# USB.net
KiCad netlist of a schematic drawn in Altium Designer
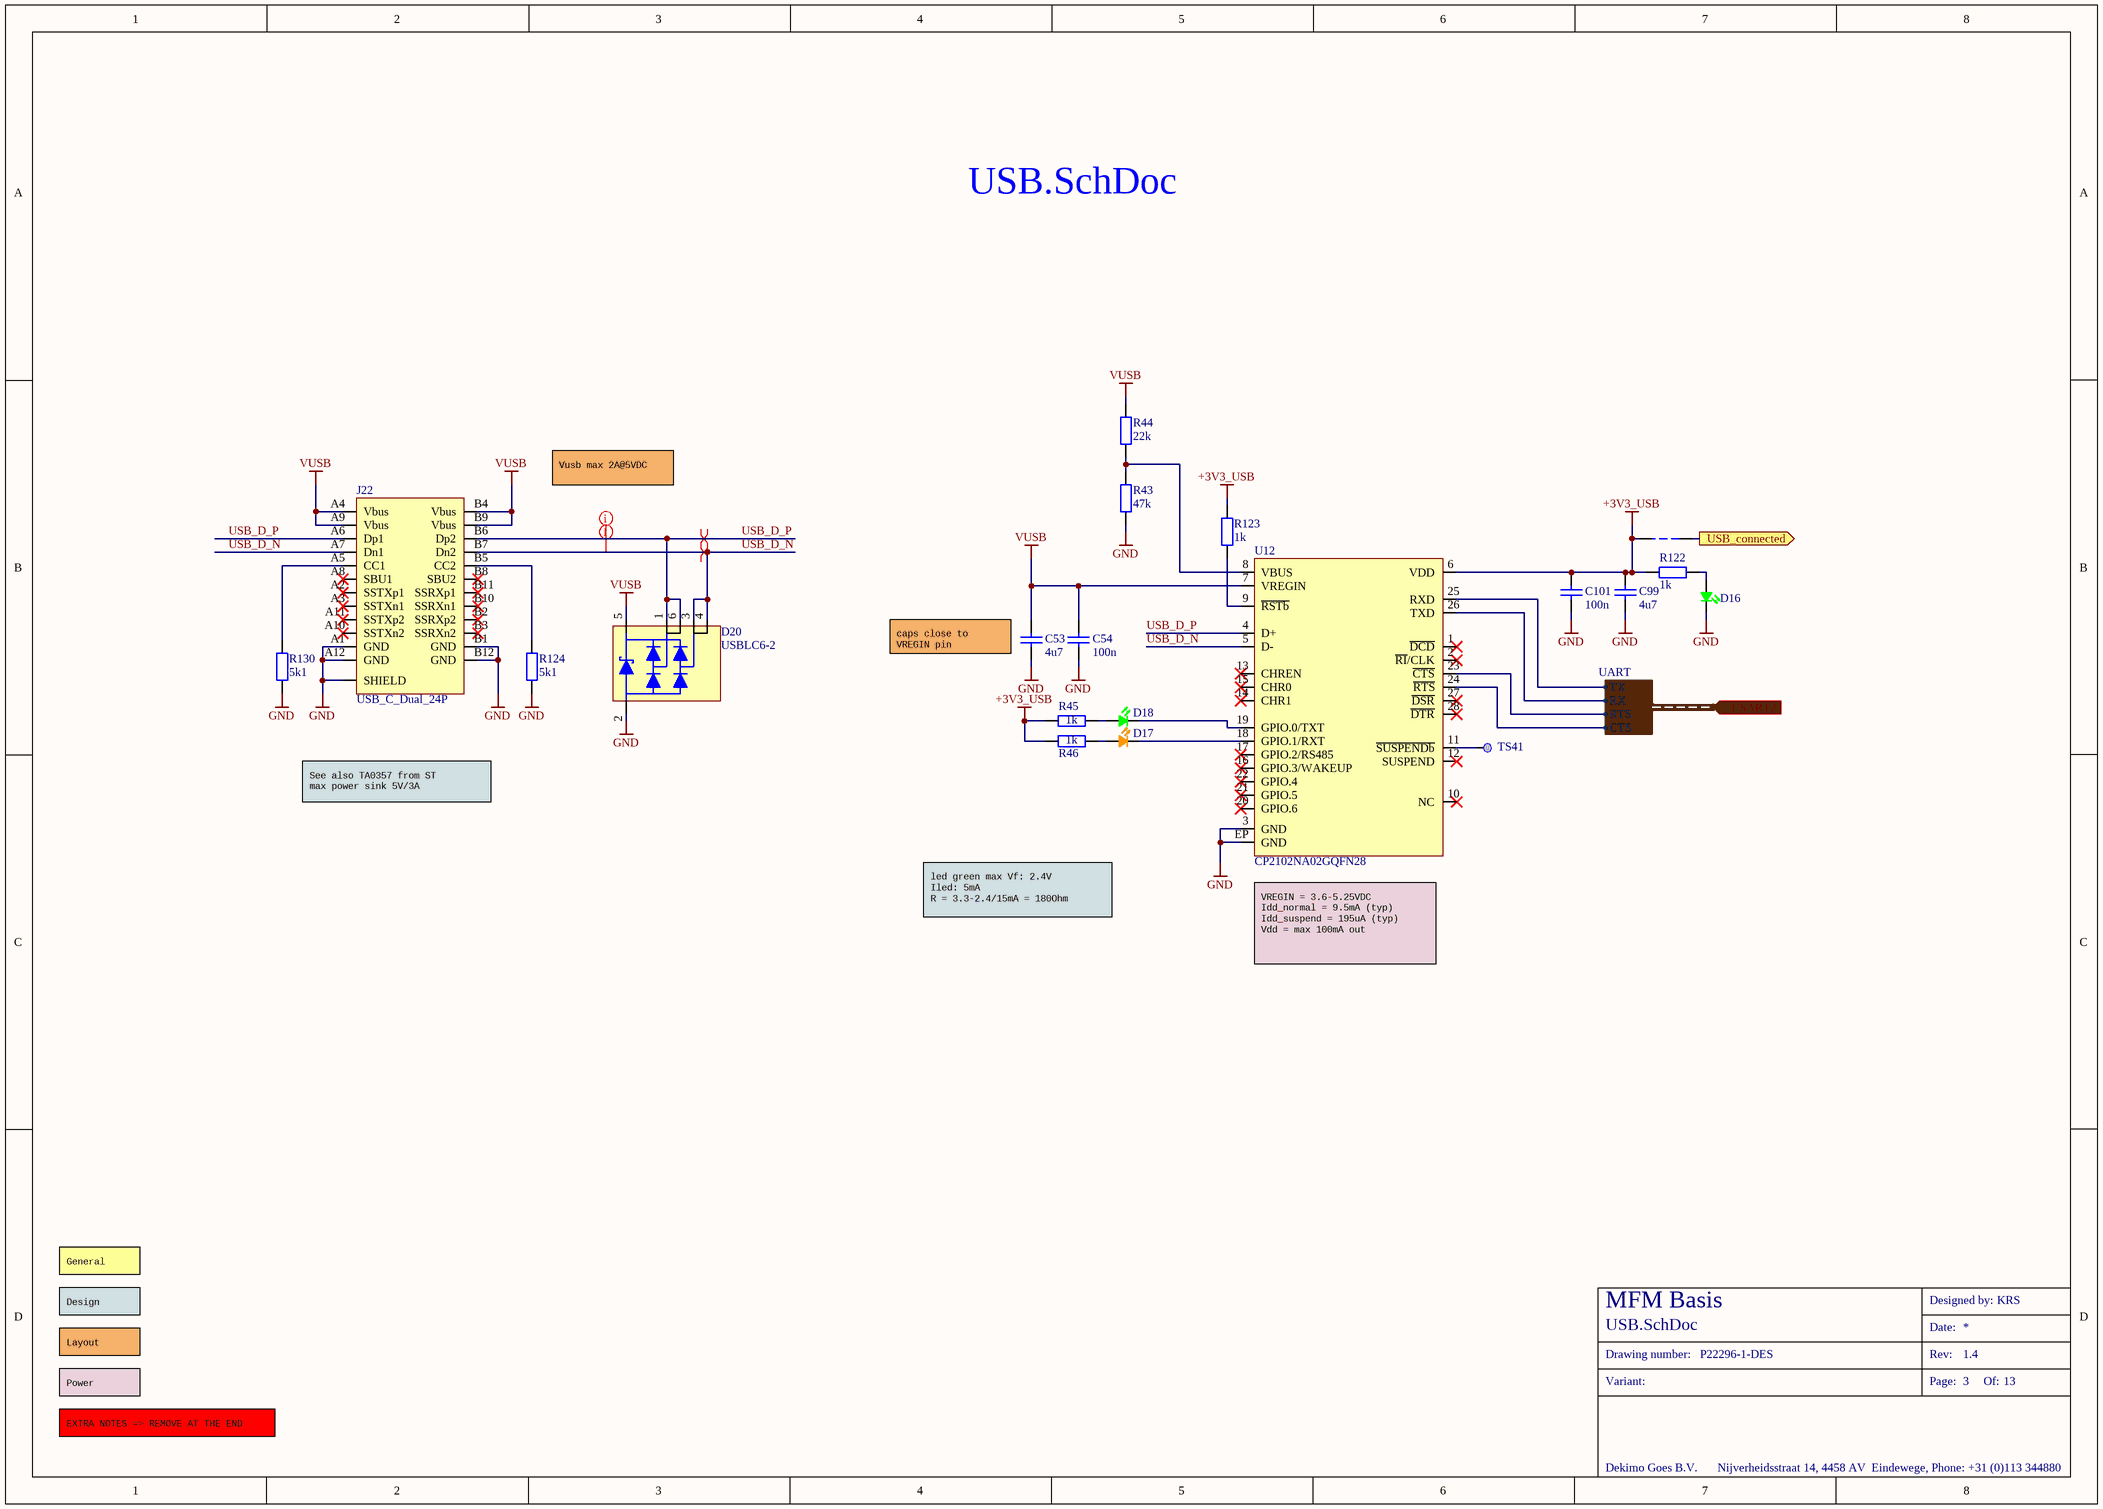
[diagram p0: USB.SchDoc]

(export (version "E")
  (design (tool "Eeschema 10.0.6"))
  (components
    (comp (ref "C53")
      (value "4u7")
      (footprint "CAPC3216X13N")
      (description "4.7uF 50V 20% X5R")
      (libsource (lib "DCI") (part "Capacitor_NP"))
    )
    (comp (ref "C54")
      (value "100n")
      (footprint "CAPC1608X09N")
      (description "100nF 50V 10% X7R")
      (libsource (lib "DCI") (part "Capacitor_NP"))
    )
    (comp (ref "C99")
      (value "4u7")
      (footprint "CAPC3216X13N")
      (description "4.7uF 50V 20% X5R")
      (libsource (lib "DCI") (part "Capacitor_NP"))
    )
    (comp (ref "C101")
      (value "100n")
      (footprint "CAPC1608X09N")
      (description "100nF 50V 10% X7R")
      (libsource (lib "DCI") (part "Capacitor_NP"))
    )
    (comp (ref "D16")
      (value "~")
      (footprint "LED_0603_ANODE")
      (description "Led Groen 0603")
      (libsource (lib "DCI") (part "LED_GREEN"))
    )
    (comp (ref "D17")
      (value "~")
      (footprint "LED_0603")
      (description "Led Orange 0603")
      (libsource (lib "DCI") (part "LED_AMBER"))
    )
    (comp (ref "D18")
      (value "~")
      (footprint "LED_0603_ANODE")
      (description "Led Groen 0603")
      (libsource (lib "DCI") (part "LED_GREEN"))
    )
    (comp (ref "D20")
      (value "USBLC6-2")
      (footprint "SOT95P280X110-6N")
      (description "USB2 protector, 15kV/8kV")
      (libsource (lib "DCI") (part "USBLC6-2"))
    )
    (comp (ref "J22")
      (value "USB_C_Dual_24P")
      (footprint "CON-009G000-024")
      (description "USB C vertical entry")
      (libsource (lib "DCI") (part "USB_C_Dual_24P"))
    )
    (comp (ref "NT1")
      (value "NET_TIE2")
      (footprint "NET_TIE_02MM")
      (description "Net-Tie for 2 Nets")
      (libsource (lib "PCBComponenten") (part "NET_TIE"))
    )
    (comp (ref "R43")
      (value "47k")
      (footprint "RESC1608X13N")
      (description "47k 100mW 1%")
      (libsource (lib "DCI") (part "Resistor"))
    )
    (comp (ref "R44")
      (value "22k")
      (footprint "RESC1608X13N")
      (description "22K 0.1W 1%")
      (libsource (lib "DCI") (part "Resistor"))
    )
    (comp (ref "R45")
      (value "1k")
      (footprint "RESC1608X13N")
      (description "1K, 100mW, 1%")
      (libsource (lib "") (part "Resistor_1"))
    )
    (comp (ref "R46")
      (value "1k")
      (footprint "RESC1608X13N")
      (description "1K, 100mW, 1%")
      (libsource (lib "") (part "Resistor_1"))
    )
    (comp (ref "R122")
      (value "1k")
      (footprint "RESC1608X13N")
      (description "1K, 100mW, 1%")
      (libsource (lib "") (part "Resistor_2"))
    )
    (comp (ref "R123")
      (value "1k")
      (footprint "RESC1608X13N")
      (description "1K, 100mW, 1%")
      (libsource (lib "DCI") (part "Resistor"))
    )
    (comp (ref "R124")
      (value "5k1")
      (footprint "RESC1608X13N")
      (description "5k1 0.1W 5%")
      (libsource (lib "DCI") (part "Resistor"))
    )
    (comp (ref "R130")
      (value "5k1")
      (footprint "RESC1608X13N")
      (description "5k1 0.1W 5%")
      (libsource (lib "DCI") (part "Resistor"))
    )
    (comp (ref "TS41")
      (value "TESTPAD")
      (footprint "TESTPAD 2MM")
      (description "0.5mm Testpad SMD")
      (libsource (lib "PCBComponenten") (part "TESTPAD"))
    )
    (comp (ref "U12")
      (value "CP2102NA02GQFN28")
      (footprint "QFN28_5x5mmP0.5")
      (description "USB to UART Bridge")
      (libsource (lib "DCI") (part "USB_CP2102N-A02-GQFN28"))
    )
  )
  (nets
    (net (code "2") (name "+3V3_USB") (class "Default")
      (node (ref "C101") (pin "2") (pinfunction "2_2") (pintype "passive"))
      (node (ref "C99") (pin "2") (pinfunction "2_2") (pintype "passive"))
      (node (ref "NT1") (pin "2") (pinfunction "2_2") (pintype "passive"))
      (node (ref "R122") (pin "1") (pinfunction "1_1") (pintype "passive"))
      (node (ref "R123") (pin "2") (pinfunction "2_2") (pintype "passive"))
      (node (ref "R45") (pin "2") (pinfunction "2_2") (pintype "passive"))
      (node (ref "R46") (pin "2") (pinfunction "2_2") (pintype "passive"))
      (node (ref "U12") (pin "6") (pinfunction "VDD_6") (pintype "passive"))
    )
    (net (code "3") (name "/CTS") (class "Default")
      (node (ref "U12") (pin "24") (pinfunction "~{RTS}_24") (pintype "passive"))
    )
    (net (code "4") (name "/RTS") (class "Default")
      (node (ref "U12") (pin "23") (pinfunction "~{CTS}_23") (pintype "passive"))
    )
    (net (code "5") (name "/RX") (class "Default")
      (node (ref "U12") (pin "26") (pinfunction "TXD_26") (pintype "passive"))
    )
    (net (code "6") (name "/TX") (class "Default")
      (node (ref "U12") (pin "25") (pinfunction "RXD_25") (pintype "passive"))
    )
    (net (code "7") (name "/USB_D_N") (class "Default")
      (node (ref "D20") (pin "3") (pinfunction "A_3") (pintype "passive"))
      (node (ref "D20") (pin "4") (pinfunction "A_4") (pintype "passive"))
      (node (ref "J22") (pin "A7") (pinfunction "Dn1_A7") (pintype "passive"))
      (node (ref "J22") (pin "B7") (pinfunction "Dn2_B7") (pintype "passive"))
      (node (ref "U12") (pin "5") (pinfunction "D-_5") (pintype "passive"))
    )
    (net (code "8") (name "/USB_D_P") (class "Default")
      (node (ref "D20") (pin "1") (pinfunction "A_1") (pintype "passive"))
      (node (ref "D20") (pin "6") (pinfunction "A_6") (pintype "passive"))
      (node (ref "J22") (pin "A6") (pinfunction "Dp1_A6") (pintype "passive"))
      (node (ref "J22") (pin "B6") (pinfunction "Dp2_B6") (pintype "passive"))
      (node (ref "U12") (pin "4") (pinfunction "D+_4") (pintype "passive"))
    )
    (net (code "9") (name "/USB_connected") (class "Default")
      (node (ref "NT1") (pin "1") (pinfunction "1_1") (pintype "passive"))
    )
    (net (code "11") (name "GND") (class "Default")
      (node (ref "C101") (pin "1") (pinfunction "1_1") (pintype "passive"))
      (node (ref "C53") (pin "1") (pinfunction "1_1") (pintype "passive"))
      (node (ref "C54") (pin "1") (pinfunction "1_1") (pintype "passive"))
      (node (ref "C99") (pin "1") (pinfunction "1_1") (pintype "passive"))
      (node (ref "D16") (pin "C") (pinfunction "C_C") (pintype "passive"))
      (node (ref "D20") (pin "2") (pinfunction "A_2") (pintype "passive"))
      (node (ref "J22") (pin "A1") (pinfunction "GND_A1") (pintype "passive"))
      (node (ref "J22") (pin "A12") (pinfunction "GND_A12") (pintype "passive"))
      (node (ref "J22") (pin "B1") (pinfunction "GND_B1") (pintype "passive"))
      (node (ref "J22") (pin "B12") (pinfunction "GND_B12") (pintype "passive"))
      (node (ref "J22") (pin "S") (pinfunction "SHIELD_S") (pintype "passive"))
      (node (ref "R124") (pin "1") (pinfunction "1_1") (pintype "passive"))
      (node (ref "R130") (pin "1") (pinfunction "1_1") (pintype "passive"))
      (node (ref "R43") (pin "1") (pinfunction "1_1") (pintype "passive"))
      (node (ref "U12") (pin "3") (pinfunction "GND_3") (pintype "passive"))
      (node (ref "U12") (pin "EP") (pinfunction "GND_EP") (pintype "passive"))
    )
    (net (code "12") (name "Net-(D16-PadA)") (class "Default")
      (node (ref "D16") (pin "A") (pinfunction "A_A") (pintype "passive"))
      (node (ref "R122") (pin "2") (pinfunction "2_2") (pintype "passive"))
    )
    (net (code "13") (name "Net-(D17-PadA)") (class "Default")
      (node (ref "D17") (pin "A") (pinfunction "A_A") (pintype "passive"))
      (node (ref "R46") (pin "1") (pinfunction "1_1") (pintype "passive"))
    )
    (net (code "14") (name "Net-(D18-PadA)") (class "Default")
      (node (ref "D18") (pin "A") (pinfunction "A_A") (pintype "passive"))
      (node (ref "R45") (pin "1") (pinfunction "1_1") (pintype "passive"))
    )
    (net (code "15") (name "Net-(J22-CC1)") (class "Default")
      (node (ref "J22") (pin "A5") (pinfunction "CC1_A5") (pintype "passive"))
      (node (ref "R130") (pin "2") (pinfunction "2_2") (pintype "passive"))
    )
    (net (code "16") (name "Net-(J22-CC2)") (class "Default")
      (node (ref "J22") (pin "B5") (pinfunction "CC2_B5") (pintype "passive"))
      (node (ref "R124") (pin "2") (pinfunction "2_2") (pintype "passive"))
    )
    (net (code "17") (name "Net-(TS41-TP)") (class "Default")
      (node (ref "TS41") (pin "1") (pinfunction "TP_1") (pintype "passive"))
      (node (ref "U12") (pin "11") (pinfunction "~{SUSPENDb}_11") (pintype "passive"))
    )
    (net (code "18") (name "Net-(U12-GPIO.0{slash}TXT)") (class "Default")
      (node (ref "D18") (pin "C") (pinfunction "C_C") (pintype "passive"))
      (node (ref "U12") (pin "19") (pinfunction "GPIO.0/TXT_19") (pintype "passive"))
    )
    (net (code "19") (name "Net-(U12-GPIO.1{slash}RXT)") (class "Default")
      (node (ref "D17") (pin "C") (pinfunction "C_C") (pintype "passive"))
      (node (ref "U12") (pin "18") (pinfunction "GPIO.1/RXT_18") (pintype "passive"))
    )
    (net (code "20") (name "Net-(U12-VBUS)") (class "Default")
      (node (ref "R43") (pin "2") (pinfunction "2_2") (pintype "passive"))
      (node (ref "R44") (pin "1") (pinfunction "1_1") (pintype "passive"))
      (node (ref "U12") (pin "8") (pinfunction "VBUS_8") (pintype "passive"))
    )
    (net (code "21") (name "Net-(U12-~{RSTb})") (class "Default")
      (node (ref "R123") (pin "1") (pinfunction "1_1") (pintype "passive"))
      (node (ref "U12") (pin "9") (pinfunction "~{RSTb}_9") (pintype "passive"))
    )
    (net (code "22") (name "VUSB") (class "Default")
      (node (ref "C53") (pin "2") (pinfunction "2_2") (pintype "passive"))
      (node (ref "C54") (pin "2") (pinfunction "2_2") (pintype "passive"))
      (node (ref "D20") (pin "5") (pinfunction "A_5") (pintype "passive"))
      (node (ref "J22") (pin "A4") (pinfunction "Vbus_A4") (pintype "passive"))
      (node (ref "J22") (pin "A9") (pinfunction "Vbus_A9") (pintype "passive"))
      (node (ref "J22") (pin "B4") (pinfunction "Vbus_B4") (pintype "passive"))
      (node (ref "J22") (pin "B9") (pinfunction "Vbus_B9") (pintype "passive"))
      (node (ref "R44") (pin "2") (pinfunction "2_2") (pintype "passive"))
      (node (ref "U12") (pin "7") (pinfunction "VREGIN_7") (pintype "passive"))
    )
    (net (code "23") (name "unconnected-(J22-SBU1-PadA8)") (class "Default")
      (node (ref "J22") (pin "A8") (pinfunction "SBU1_A8") (pintype "passive+no_connect"))
    )
    (net (code "24") (name "unconnected-(J22-SBU2-PadB8)") (class "Default")
      (node (ref "J22") (pin "B8") (pinfunction "SBU2_B8") (pintype "passive+no_connect"))
    )
    (net (code "25") (name "unconnected-(J22-SSRXn1-PadB10)") (class "Default")
      (node (ref "J22") (pin "B10") (pinfunction "SSRXn1_B10") (pintype "passive+no_connect"))
    )
    (net (code "26") (name "unconnected-(J22-SSRXn2-PadB3)") (class "Default")
      (node (ref "J22") (pin "B3") (pinfunction "SSRXn2_B3") (pintype "passive+no_connect"))
    )
    (net (code "27") (name "unconnected-(J22-SSRXp1-PadB11)") (class "Default")
      (node (ref "J22") (pin "B11") (pinfunction "SSRXp1_B11") (pintype "passive+no_connect"))
    )
    (net (code "28") (name "unconnected-(J22-SSRXp2-PadB2)") (class "Default")
      (node (ref "J22") (pin "B2") (pinfunction "SSRXp2_B2") (pintype "passive+no_connect"))
    )
    (net (code "29") (name "unconnected-(J22-SSTXn1-PadA3)") (class "Default")
      (node (ref "J22") (pin "A3") (pinfunction "SSTXn1_A3") (pintype "passive+no_connect"))
    )
    (net (code "30") (name "unconnected-(J22-SSTXn2-PadA10)") (class "Default")
      (node (ref "J22") (pin "A10") (pinfunction "SSTXn2_A10") (pintype "passive+no_connect"))
    )
    (net (code "31") (name "unconnected-(J22-SSTXp1-PadA2)") (class "Default")
      (node (ref "J22") (pin "A2") (pinfunction "SSTXp1_A2") (pintype "passive+no_connect"))
    )
    (net (code "32") (name "unconnected-(J22-SSTXp2-PadA11)") (class "Default")
      (node (ref "J22") (pin "A11") (pinfunction "SSTXp2_A11") (pintype "passive+no_connect"))
    )
    (net (code "33") (name "unconnected-(U12-CHR0-Pad15)") (class "Default")
      (node (ref "U12") (pin "15") (pinfunction "CHR0_15") (pintype "passive+no_connect"))
    )
    (net (code "34") (name "unconnected-(U12-CHR1-Pad14)") (class "Default")
      (node (ref "U12") (pin "14") (pinfunction "CHR1_14") (pintype "passive+no_connect"))
    )
    (net (code "35") (name "unconnected-(U12-CHREN-Pad13)") (class "Default")
      (node (ref "U12") (pin "13") (pinfunction "CHREN_13") (pintype "passive+no_connect"))
    )
    (net (code "36") (name "unconnected-(U12-GPIO.2{slash}RS485-Pad17)") (class "Default")
      (node (ref "U12") (pin "17") (pinfunction "GPIO.2/RS485_17") (pintype "passive+no_connect"))
    )
    (net (code "37") (name "unconnected-(U12-GPIO.3{slash}WAKEUP-Pad16)") (class "Default")
      (node (ref "U12") (pin "16") (pinfunction "GPIO.3/WAKEUP_16") (pintype "passive+no_connect"))
    )
    (net (code "38") (name "unconnected-(U12-GPIO.4-Pad22)") (class "Default")
      (node (ref "U12") (pin "22") (pinfunction "GPIO.4_22") (pintype "passive+no_connect"))
    )
    (net (code "39") (name "unconnected-(U12-GPIO.5-Pad21)") (class "Default")
      (node (ref "U12") (pin "21") (pinfunction "GPIO.5_21") (pintype "passive+no_connect"))
    )
    (net (code "40") (name "unconnected-(U12-GPIO.6-Pad20)") (class "Default")
      (node (ref "U12") (pin "20") (pinfunction "GPIO.6_20") (pintype "passive+no_connect"))
    )
    (net (code "41") (name "unconnected-(U12-NC-Pad10)") (class "Default")
      (node (ref "U12") (pin "10") (pinfunction "NC_10") (pintype "passive+no_connect"))
    )
    (net (code "42") (name "unconnected-(U12-SUSPEND-Pad12)") (class "Default")
      (node (ref "U12") (pin "12") (pinfunction "SUSPEND_12") (pintype "passive+no_connect"))
    )
    (net (code "43") (name "unconnected-(U12-~{DCD}-Pad1)") (class "Default")
      (node (ref "U12") (pin "1") (pinfunction "~{DCD}_1") (pintype "passive+no_connect"))
    )
    (net (code "44") (name "unconnected-(U12-~{DSR}-Pad27)") (class "Default")
      (node (ref "U12") (pin "27") (pinfunction "~{DSR}_27") (pintype "passive+no_connect"))
    )
    (net (code "45") (name "unconnected-(U12-~{DTR}-Pad28)") (class "Default")
      (node (ref "U12") (pin "28") (pinfunction "~{DTR}_28") (pintype "passive+no_connect"))
    )
    (net (code "46") (name "unconnected-(U12-~{RI}{slash}CLK-Pad2)") (class "Default")
      (node (ref "U12") (pin "2") (pinfunction "~{RI}/CLK_2") (pintype "passive+no_connect"))
    )
  )
)
